# parallel_trans.net
KiCad netlist of a schematic drawn in EasyEDA Pro
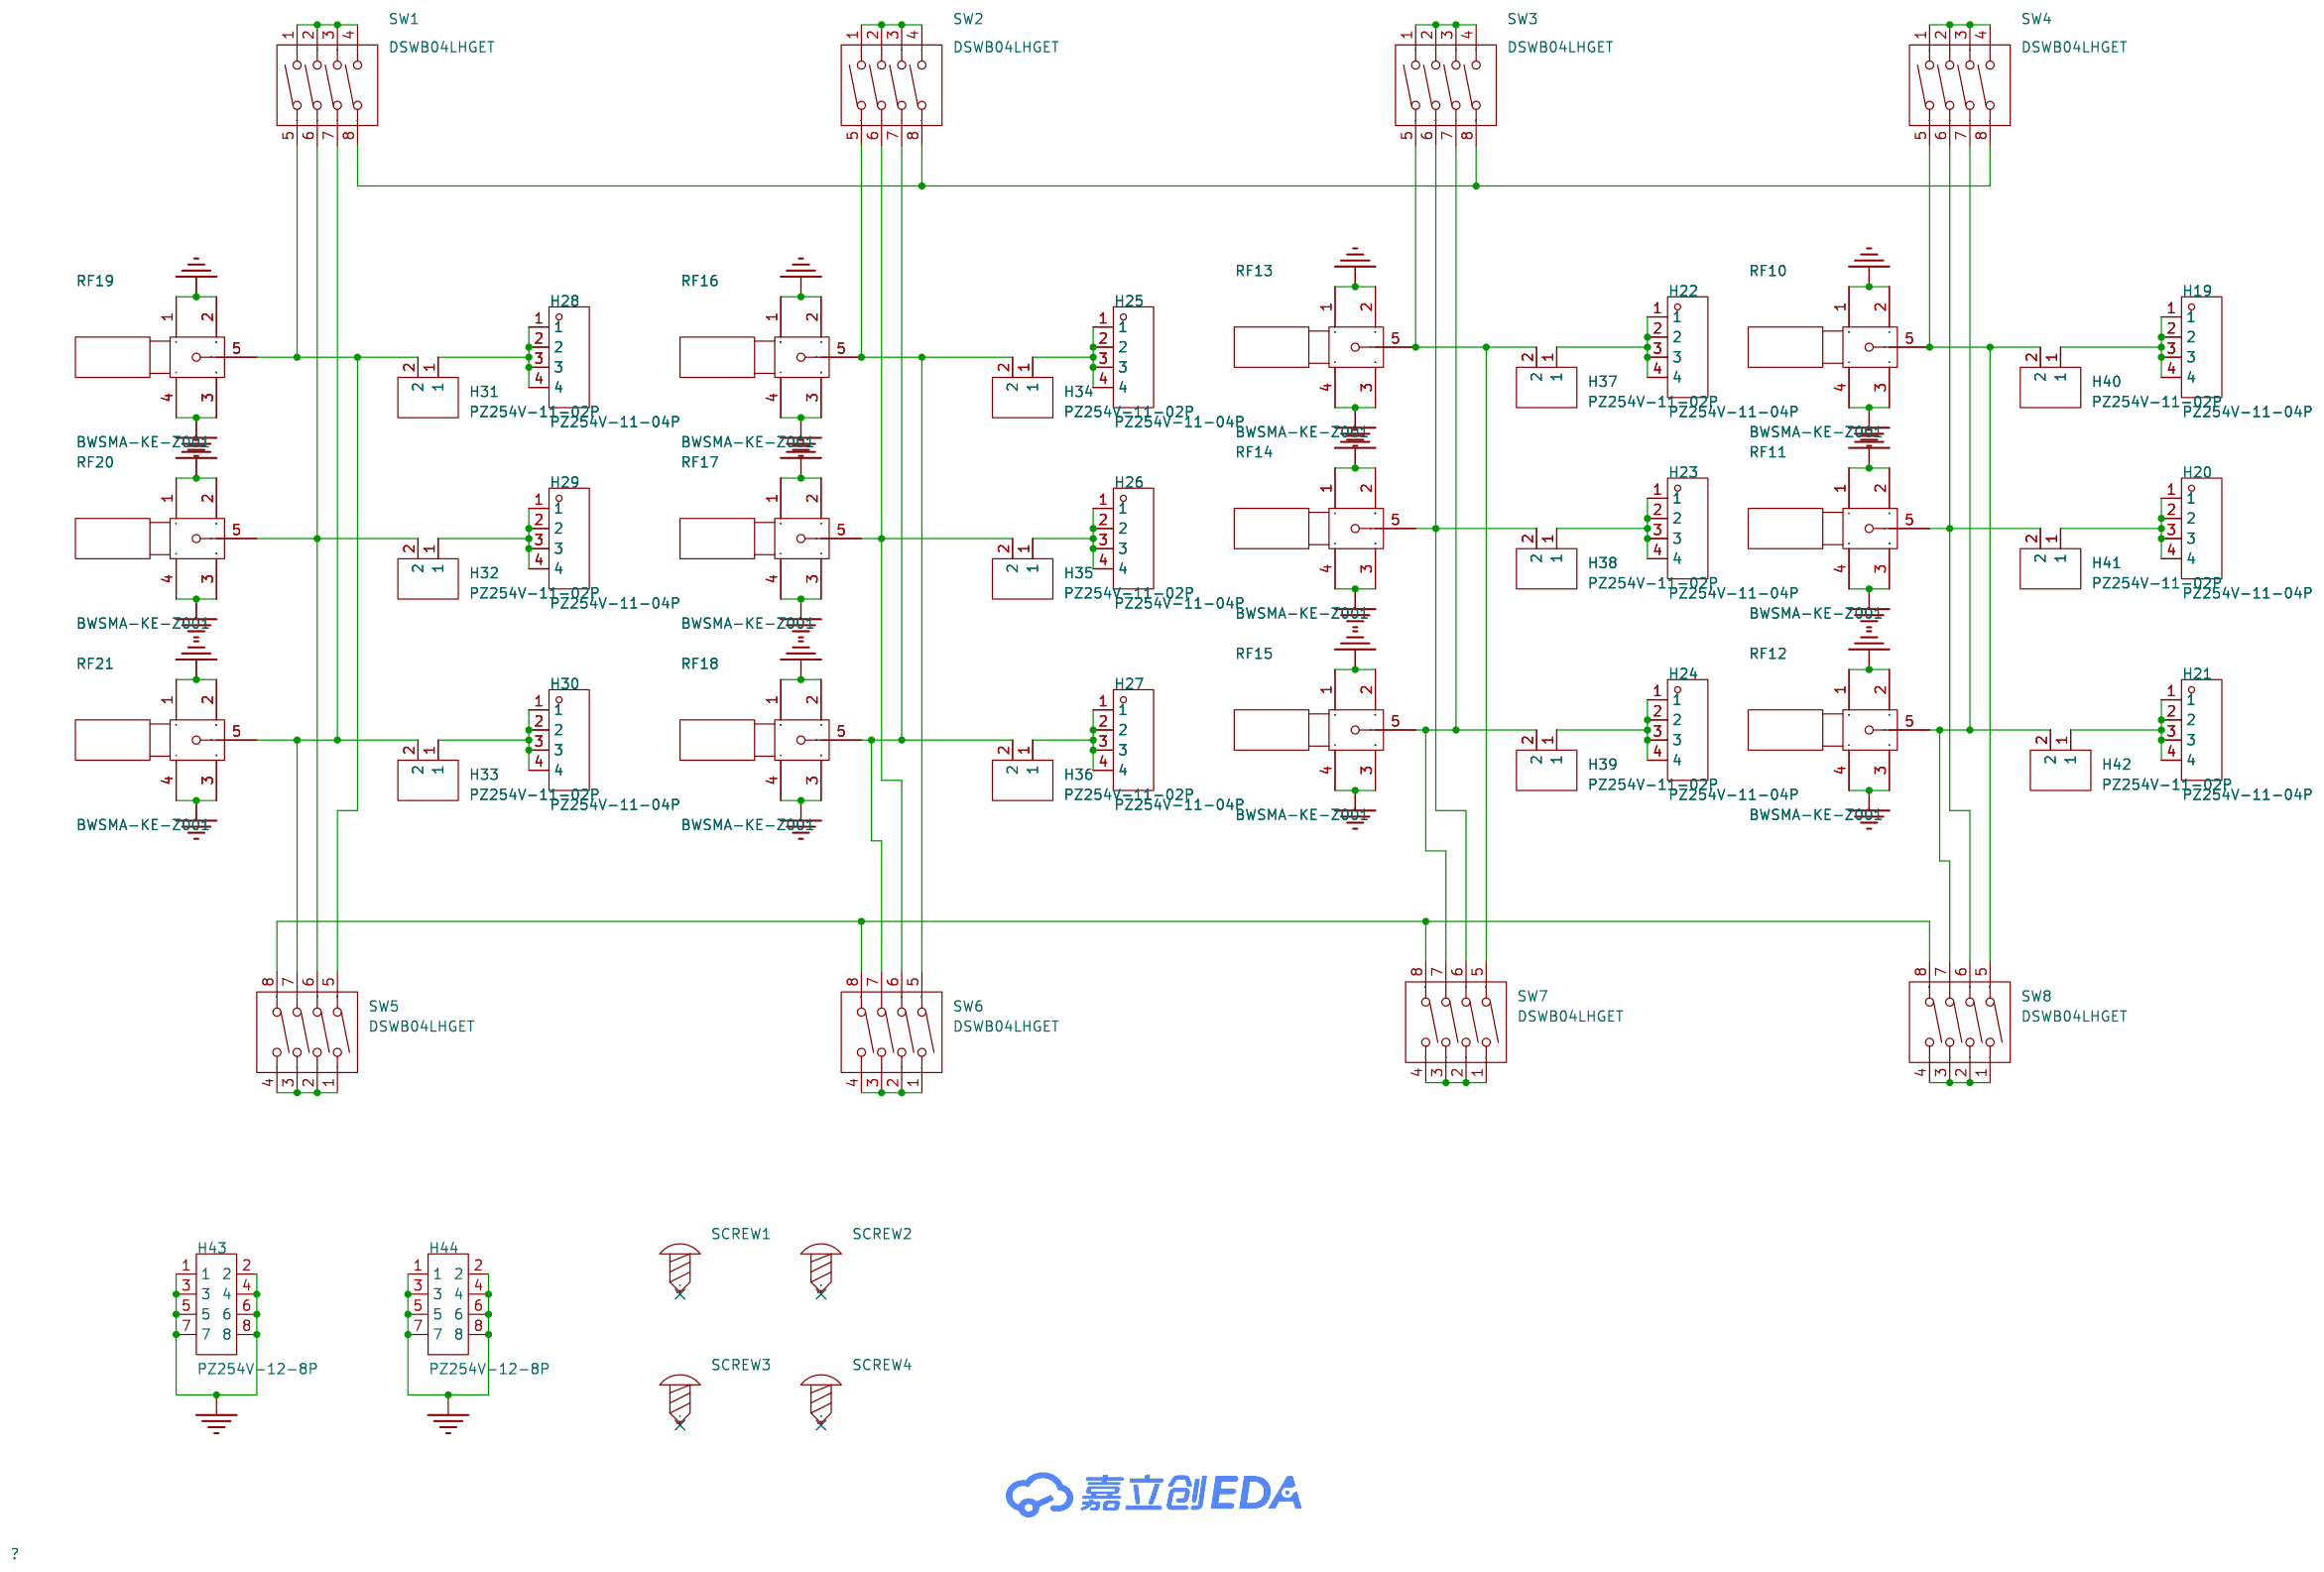
[diagram p0: schematic sheet]

(export (version "E")
  (design (tool "Eeschema 10.0.6"))
  (components
    (comp (ref "H19")
      (value "PZ254V-11-04P")
      (footprint "easyedapro:HDR-TH_4P-P2.54-V-M")
      (fields (field (name "Manufacturer") "XFCN(兴飞)"))
      (libsource (lib "easyedapro") (part "PZ254V-11-04P_C2691448"))
    )
    (comp (ref "H20")
      (value "PZ254V-11-04P")
      (footprint "easyedapro:HDR-TH_4P-P2.54-V-M")
      (fields (field (name "Manufacturer") "XFCN(兴飞)"))
      (libsource (lib "easyedapro") (part "PZ254V-11-04P_C2691448"))
    )
    (comp (ref "H21")
      (value "PZ254V-11-04P")
      (footprint "easyedapro:HDR-TH_4P-P2.54-V-M")
      (fields (field (name "Manufacturer") "XFCN(兴飞)"))
      (libsource (lib "easyedapro") (part "PZ254V-11-04P_C2691448"))
    )
    (comp (ref "H22")
      (value "PZ254V-11-04P")
      (footprint "easyedapro:HDR-TH_4P-P2.54-V-M")
      (fields (field (name "Manufacturer") "XFCN(兴飞)"))
      (libsource (lib "easyedapro") (part "PZ254V-11-04P_C2691448"))
    )
    (comp (ref "H23")
      (value "PZ254V-11-04P")
      (footprint "easyedapro:HDR-TH_4P-P2.54-V-M")
      (fields (field (name "Manufacturer") "XFCN(兴飞)"))
      (libsource (lib "easyedapro") (part "PZ254V-11-04P_C2691448"))
    )
    (comp (ref "H24")
      (value "PZ254V-11-04P")
      (footprint "easyedapro:HDR-TH_4P-P2.54-V-M")
      (fields (field (name "Manufacturer") "XFCN(兴飞)"))
      (libsource (lib "easyedapro") (part "PZ254V-11-04P_C2691448"))
    )
    (comp (ref "H25")
      (value "PZ254V-11-04P")
      (footprint "easyedapro:HDR-TH_4P-P2.54-V-M")
      (fields (field (name "Manufacturer") "XFCN(兴飞)"))
      (libsource (lib "easyedapro") (part "PZ254V-11-04P_C2691448"))
    )
    (comp (ref "H26")
      (value "PZ254V-11-04P")
      (footprint "easyedapro:HDR-TH_4P-P2.54-V-M")
      (fields (field (name "Manufacturer") "XFCN(兴飞)"))
      (libsource (lib "easyedapro") (part "PZ254V-11-04P_C2691448"))
    )
    (comp (ref "H27")
      (value "PZ254V-11-04P")
      (footprint "easyedapro:HDR-TH_4P-P2.54-V-M")
      (fields (field (name "Manufacturer") "XFCN(兴飞)"))
      (libsource (lib "easyedapro") (part "PZ254V-11-04P_C2691448"))
    )
    (comp (ref "H28")
      (value "PZ254V-11-04P")
      (footprint "easyedapro:HDR-TH_4P-P2.54-V-M")
      (fields (field (name "Manufacturer") "XFCN(兴飞)"))
      (libsource (lib "easyedapro") (part "PZ254V-11-04P_C2691448"))
    )
    (comp (ref "H29")
      (value "PZ254V-11-04P")
      (footprint "easyedapro:HDR-TH_4P-P2.54-V-M")
      (fields (field (name "Manufacturer") "XFCN(兴飞)"))
      (libsource (lib "easyedapro") (part "PZ254V-11-04P_C2691448"))
    )
    (comp (ref "H30")
      (value "PZ254V-11-04P")
      (footprint "easyedapro:HDR-TH_4P-P2.54-V-M")
      (fields (field (name "Manufacturer") "XFCN(兴飞)"))
      (libsource (lib "easyedapro") (part "PZ254V-11-04P_C2691448"))
    )
    (comp (ref "H31")
      (value "PZ254V-11-02P")
      (footprint "easyedapro:HDR-TH_2P-P2.54-V-M")
      (fields (field (name "Manufacturer") "XFCN(兴飞)"))
      (libsource (lib "easyedapro") (part "PZ254V-11-02P"))
    )
    (comp (ref "H32")
      (value "PZ254V-11-02P")
      (footprint "easyedapro:HDR-TH_2P-P2.54-V-M")
      (fields (field (name "Manufacturer") "XFCN(兴飞)"))
      (libsource (lib "easyedapro") (part "PZ254V-11-02P"))
    )
    (comp (ref "H33")
      (value "PZ254V-11-02P")
      (footprint "easyedapro:HDR-TH_2P-P2.54-V-M")
      (fields (field (name "Manufacturer") "XFCN(兴飞)"))
      (libsource (lib "easyedapro") (part "PZ254V-11-02P"))
    )
    (comp (ref "H34")
      (value "PZ254V-11-02P")
      (footprint "easyedapro:HDR-TH_2P-P2.54-V-M")
      (fields (field (name "Manufacturer") "XFCN(兴飞)"))
      (libsource (lib "easyedapro") (part "PZ254V-11-02P"))
    )
    (comp (ref "H35")
      (value "PZ254V-11-02P")
      (footprint "easyedapro:HDR-TH_2P-P2.54-V-M")
      (fields (field (name "Manufacturer") "XFCN(兴飞)"))
      (libsource (lib "easyedapro") (part "PZ254V-11-02P"))
    )
    (comp (ref "H36")
      (value "PZ254V-11-02P")
      (footprint "easyedapro:HDR-TH_2P-P2.54-V-M")
      (fields (field (name "Manufacturer") "XFCN(兴飞)"))
      (libsource (lib "easyedapro") (part "PZ254V-11-02P"))
    )
    (comp (ref "H37")
      (value "PZ254V-11-02P")
      (footprint "easyedapro:HDR-TH_2P-P2.54-V-M")
      (fields (field (name "Manufacturer") "XFCN(兴飞)"))
      (libsource (lib "easyedapro") (part "PZ254V-11-02P"))
    )
    (comp (ref "H38")
      (value "PZ254V-11-02P")
      (footprint "easyedapro:HDR-TH_2P-P2.54-V-M")
      (fields (field (name "Manufacturer") "XFCN(兴飞)"))
      (libsource (lib "easyedapro") (part "PZ254V-11-02P"))
    )
    (comp (ref "H39")
      (value "PZ254V-11-02P")
      (footprint "easyedapro:HDR-TH_2P-P2.54-V-M")
      (fields (field (name "Manufacturer") "XFCN(兴飞)"))
      (libsource (lib "easyedapro") (part "PZ254V-11-02P"))
    )
    (comp (ref "H40")
      (value "PZ254V-11-02P")
      (footprint "easyedapro:HDR-TH_2P-P2.54-V-M")
      (fields (field (name "Manufacturer") "XFCN(兴飞)"))
      (libsource (lib "easyedapro") (part "PZ254V-11-02P"))
    )
    (comp (ref "H41")
      (value "PZ254V-11-02P")
      (footprint "easyedapro:HDR-TH_2P-P2.54-V-M")
      (fields (field (name "Manufacturer") "XFCN(兴飞)"))
      (libsource (lib "easyedapro") (part "PZ254V-11-02P"))
    )
    (comp (ref "H42")
      (value "PZ254V-11-02P")
      (footprint "easyedapro:HDR-TH_2P-P2.54-V-M")
      (fields (field (name "Manufacturer") "XFCN(兴飞)"))
      (libsource (lib "easyedapro") (part "PZ254V-11-02P"))
    )
    (comp (ref "H43")
      (value "PZ254V-12-8P")
      (footprint "easyedapro:HDR-TH_8P-P2.54-V-M-R2-C4-S2.54")
      (fields (field (name "Manufacturer") "XFCN(兴飞)"))
      (libsource (lib "easyedapro") (part "PZ254V-12-8P"))
    )
    (comp (ref "H44")
      (value "PZ254V-12-8P")
      (footprint "easyedapro:HDR-TH_8P-P2.54-V-M-R2-C4-S2.54")
      (fields (field (name "Manufacturer") "XFCN(兴飞)"))
      (libsource (lib "easyedapro") (part "PZ254V-12-8P"))
    )
    (comp (ref "RF10")
      (value "BWSMA-KE-Z001")
      (footprint "easyedapro:SMA-TH_BWSMA-KE-Z001")
      (fields (field (name "Manufacturer") "BAT WIRELESS(蝙蝠无线)"))
      (libsource (lib "easyedapro") (part "BWSMA-KE-Z001"))
    )
    (comp (ref "RF11")
      (value "BWSMA-KE-Z001")
      (footprint "easyedapro:SMA-TH_BWSMA-KE-Z001")
      (fields (field (name "Manufacturer") "BAT WIRELESS(蝙蝠无线)"))
      (libsource (lib "easyedapro") (part "BWSMA-KE-Z001"))
    )
    (comp (ref "RF12")
      (value "BWSMA-KE-Z001")
      (footprint "easyedapro:SMA-TH_BWSMA-KE-Z001")
      (fields (field (name "Manufacturer") "BAT WIRELESS(蝙蝠无线)"))
      (libsource (lib "easyedapro") (part "BWSMA-KE-Z001"))
    )
    (comp (ref "RF13")
      (value "BWSMA-KE-Z001")
      (footprint "easyedapro:SMA-TH_BWSMA-KE-Z001")
      (fields (field (name "Manufacturer") "BAT WIRELESS(蝙蝠无线)"))
      (libsource (lib "easyedapro") (part "BWSMA-KE-Z001"))
    )
    (comp (ref "RF14")
      (value "BWSMA-KE-Z001")
      (footprint "easyedapro:SMA-TH_BWSMA-KE-Z001")
      (fields (field (name "Manufacturer") "BAT WIRELESS(蝙蝠无线)"))
      (libsource (lib "easyedapro") (part "BWSMA-KE-Z001"))
    )
    (comp (ref "RF15")
      (value "BWSMA-KE-Z001")
      (footprint "easyedapro:SMA-TH_BWSMA-KE-Z001")
      (fields (field (name "Manufacturer") "BAT WIRELESS(蝙蝠无线)"))
      (libsource (lib "easyedapro") (part "BWSMA-KE-Z001"))
    )
    (comp (ref "RF16")
      (value "BWSMA-KE-Z001")
      (footprint "easyedapro:SMA-TH_BWSMA-KE-Z001")
      (fields (field (name "Manufacturer") "BAT WIRELESS(蝙蝠无线)"))
      (libsource (lib "easyedapro") (part "BWSMA-KE-Z001"))
    )
    (comp (ref "RF17")
      (value "BWSMA-KE-Z001")
      (footprint "easyedapro:SMA-TH_BWSMA-KE-Z001")
      (fields (field (name "Manufacturer") "BAT WIRELESS(蝙蝠无线)"))
      (libsource (lib "easyedapro") (part "BWSMA-KE-Z001"))
    )
    (comp (ref "RF18")
      (value "BWSMA-KE-Z001")
      (footprint "easyedapro:SMA-TH_BWSMA-KE-Z001")
      (fields (field (name "Manufacturer") "BAT WIRELESS(蝙蝠无线)"))
      (libsource (lib "easyedapro") (part "BWSMA-KE-Z001"))
    )
    (comp (ref "RF19")
      (value "BWSMA-KE-Z001")
      (footprint "easyedapro:SMA-TH_BWSMA-KE-Z001")
      (fields (field (name "Manufacturer") "BAT WIRELESS(蝙蝠无线)"))
      (libsource (lib "easyedapro") (part "BWSMA-KE-Z001"))
    )
    (comp (ref "RF20")
      (value "BWSMA-KE-Z001")
      (footprint "easyedapro:SMA-TH_BWSMA-KE-Z001")
      (fields (field (name "Manufacturer") "BAT WIRELESS(蝙蝠无线)"))
      (libsource (lib "easyedapro") (part "BWSMA-KE-Z001"))
    )
    (comp (ref "RF21")
      (value "BWSMA-KE-Z001")
      (footprint "easyedapro:SMA-TH_BWSMA-KE-Z001")
      (fields (field (name "Manufacturer") "BAT WIRELESS(蝙蝠无线)"))
      (libsource (lib "easyedapro") (part "BWSMA-KE-Z001"))
    )
    (comp (ref "SCREW1")
      (value "~")
      (footprint "easyedapro:M3螺丝")
      (libsource (lib "easyedapro") (part "螺丝孔"))
    )
    (comp (ref "SCREW2")
      (value "~")
      (footprint "easyedapro:M3螺丝")
      (libsource (lib "easyedapro") (part "螺丝孔"))
    )
    (comp (ref "SCREW3")
      (value "~")
      (footprint "easyedapro:M3螺丝")
      (libsource (lib "easyedapro") (part "螺丝孔"))
    )
    (comp (ref "SCREW4")
      (value "~")
      (footprint "easyedapro:M3螺丝")
      (libsource (lib "easyedapro") (part "螺丝孔"))
    )
    (comp (ref "SW1")
      (value "DSWB04LHGET")
      (footprint "easyedapro:SW-TH_DSWB04LHGET")
      (description "类型:平拨,凸起式;电路结构:单刀单掷;开关位数:4位;使用寿命:-;颜色:红色;")
      (fields (field (name "Manufacturer") "YE"))
      (libsource (lib "easyedapro") (part "DSWB04LHGET"))
    )
    (comp (ref "SW2")
      (value "DSWB04LHGET")
      (footprint "easyedapro:SW-TH_DSWB04LHGET")
      (description "类型:平拨,凸起式;电路结构:单刀单掷;开关位数:4位;使用寿命:-;颜色:红色;")
      (fields (field (name "Manufacturer") "YE"))
      (libsource (lib "easyedapro") (part "DSWB04LHGET"))
    )
    (comp (ref "SW3")
      (value "DSWB04LHGET")
      (footprint "easyedapro:SW-TH_DSWB04LHGET")
      (description "类型:平拨,凸起式;电路结构:单刀单掷;开关位数:4位;使用寿命:-;颜色:红色;")
      (fields (field (name "Manufacturer") "YE"))
      (libsource (lib "easyedapro") (part "DSWB04LHGET"))
    )
    (comp (ref "SW4")
      (value "DSWB04LHGET")
      (footprint "easyedapro:SW-TH_DSWB04LHGET")
      (description "类型:平拨,凸起式;电路结构:单刀单掷;开关位数:4位;使用寿命:-;颜色:红色;")
      (fields (field (name "Manufacturer") "YE"))
      (libsource (lib "easyedapro") (part "DSWB04LHGET"))
    )
    (comp (ref "SW5")
      (value "DSWB04LHGET")
      (footprint "easyedapro:SW-TH_DSWB04LHGET")
      (description "类型:平拨,凸起式;电路结构:单刀单掷;开关位数:4位;使用寿命:-;颜色:红色;")
      (fields (field (name "Manufacturer") "YE"))
      (libsource (lib "easyedapro") (part "DSWB04LHGET"))
    )
    (comp (ref "SW6")
      (value "DSWB04LHGET")
      (footprint "easyedapro:SW-TH_DSWB04LHGET")
      (description "类型:平拨,凸起式;电路结构:单刀单掷;开关位数:4位;使用寿命:-;颜色:红色;")
      (fields (field (name "Manufacturer") "YE"))
      (libsource (lib "easyedapro") (part "DSWB04LHGET"))
    )
    (comp (ref "SW7")
      (value "DSWB04LHGET")
      (footprint "easyedapro:SW-TH_DSWB04LHGET")
      (description "类型:平拨,凸起式;电路结构:单刀单掷;开关位数:4位;使用寿命:-;颜色:红色;")
      (fields (field (name "Manufacturer") "YE"))
      (libsource (lib "easyedapro") (part "DSWB04LHGET"))
    )
    (comp (ref "SW8")
      (value "DSWB04LHGET")
      (footprint "easyedapro:SW-TH_DSWB04LHGET")
      (description "类型:平拨,凸起式;电路结构:单刀单掷;开关位数:4位;使用寿命:-;颜色:红色;")
      (fields (field (name "Manufacturer") "YE"))
      (libsource (lib "easyedapro") (part "DSWB04LHGET"))
    )
  )
  (nets
    (net (code "1") (name "GND") (class "Default")
      (node (ref "H43") (pin "1") (pinfunction "1_1") (pintype "unspecified"))
      (node (ref "H43") (pin "2") (pinfunction "2_2") (pintype "unspecified"))
      (node (ref "H43") (pin "3") (pinfunction "3_3") (pintype "unspecified"))
      (node (ref "H43") (pin "4") (pinfunction "4_4") (pintype "unspecified"))
      (node (ref "H43") (pin "5") (pinfunction "5_5") (pintype "unspecified"))
      (node (ref "H43") (pin "6") (pinfunction "6_6") (pintype "unspecified"))
      (node (ref "H43") (pin "7") (pinfunction "7_7") (pintype "unspecified"))
      (node (ref "H43") (pin "8") (pinfunction "8_8") (pintype "unspecified"))
      (node (ref "H44") (pin "1") (pinfunction "1_1") (pintype "unspecified"))
      (node (ref "H44") (pin "2") (pinfunction "2_2") (pintype "unspecified"))
      (node (ref "H44") (pin "3") (pinfunction "3_3") (pintype "unspecified"))
      (node (ref "H44") (pin "4") (pinfunction "4_4") (pintype "unspecified"))
      (node (ref "H44") (pin "5") (pinfunction "5_5") (pintype "unspecified"))
      (node (ref "H44") (pin "6") (pinfunction "6_6") (pintype "unspecified"))
      (node (ref "H44") (pin "7") (pinfunction "7_7") (pintype "unspecified"))
      (node (ref "H44") (pin "8") (pinfunction "8_8") (pintype "unspecified"))
      (node (ref "RF10") (pin "1") (pinfunction "1_1") (pintype "unspecified"))
      (node (ref "RF10") (pin "2") (pinfunction "2_2") (pintype "unspecified"))
      (node (ref "RF10") (pin "3") (pinfunction "3_3") (pintype "unspecified"))
      (node (ref "RF10") (pin "4") (pinfunction "4_4") (pintype "unspecified"))
      (node (ref "RF11") (pin "1") (pinfunction "1_1") (pintype "unspecified"))
      (node (ref "RF11") (pin "2") (pinfunction "2_2") (pintype "unspecified"))
      (node (ref "RF11") (pin "3") (pinfunction "3_3") (pintype "unspecified"))
      (node (ref "RF11") (pin "4") (pinfunction "4_4") (pintype "unspecified"))
      (node (ref "RF12") (pin "1") (pinfunction "1_1") (pintype "unspecified"))
      (node (ref "RF12") (pin "2") (pinfunction "2_2") (pintype "unspecified"))
      (node (ref "RF12") (pin "3") (pinfunction "3_3") (pintype "unspecified"))
      (node (ref "RF12") (pin "4") (pinfunction "4_4") (pintype "unspecified"))
      (node (ref "RF13") (pin "1") (pinfunction "1_1") (pintype "unspecified"))
      (node (ref "RF13") (pin "2") (pinfunction "2_2") (pintype "unspecified"))
      (node (ref "RF13") (pin "3") (pinfunction "3_3") (pintype "unspecified"))
      (node (ref "RF13") (pin "4") (pinfunction "4_4") (pintype "unspecified"))
      (node (ref "RF14") (pin "1") (pinfunction "1_1") (pintype "unspecified"))
      (node (ref "RF14") (pin "2") (pinfunction "2_2") (pintype "unspecified"))
      (node (ref "RF14") (pin "3") (pinfunction "3_3") (pintype "unspecified"))
      (node (ref "RF14") (pin "4") (pinfunction "4_4") (pintype "unspecified"))
      (node (ref "RF15") (pin "1") (pinfunction "1_1") (pintype "unspecified"))
      (node (ref "RF15") (pin "2") (pinfunction "2_2") (pintype "unspecified"))
      (node (ref "RF15") (pin "3") (pinfunction "3_3") (pintype "unspecified"))
      (node (ref "RF15") (pin "4") (pinfunction "4_4") (pintype "unspecified"))
      (node (ref "RF16") (pin "1") (pinfunction "1_1") (pintype "unspecified"))
      (node (ref "RF16") (pin "2") (pinfunction "2_2") (pintype "unspecified"))
      (node (ref "RF16") (pin "3") (pinfunction "3_3") (pintype "unspecified"))
      (node (ref "RF16") (pin "4") (pinfunction "4_4") (pintype "unspecified"))
      (node (ref "RF17") (pin "1") (pinfunction "1_1") (pintype "unspecified"))
      (node (ref "RF17") (pin "2") (pinfunction "2_2") (pintype "unspecified"))
      (node (ref "RF17") (pin "3") (pinfunction "3_3") (pintype "unspecified"))
      (node (ref "RF17") (pin "4") (pinfunction "4_4") (pintype "unspecified"))
      (node (ref "RF18") (pin "1") (pinfunction "1_1") (pintype "unspecified"))
      (node (ref "RF18") (pin "2") (pinfunction "2_2") (pintype "unspecified"))
      (node (ref "RF18") (pin "3") (pinfunction "3_3") (pintype "unspecified"))
      (node (ref "RF18") (pin "4") (pinfunction "4_4") (pintype "unspecified"))
      (node (ref "RF19") (pin "1") (pinfunction "1_1") (pintype "unspecified"))
      (node (ref "RF19") (pin "2") (pinfunction "2_2") (pintype "unspecified"))
      (node (ref "RF19") (pin "3") (pinfunction "3_3") (pintype "unspecified"))
      (node (ref "RF19") (pin "4") (pinfunction "4_4") (pintype "unspecified"))
      (node (ref "RF20") (pin "1") (pinfunction "1_1") (pintype "unspecified"))
      (node (ref "RF20") (pin "2") (pinfunction "2_2") (pintype "unspecified"))
      (node (ref "RF20") (pin "3") (pinfunction "3_3") (pintype "unspecified"))
      (node (ref "RF20") (pin "4") (pinfunction "4_4") (pintype "unspecified"))
      (node (ref "RF21") (pin "1") (pinfunction "1_1") (pintype "unspecified"))
      (node (ref "RF21") (pin "2") (pinfunction "2_2") (pintype "unspecified"))
      (node (ref "RF21") (pin "3") (pinfunction "3_3") (pintype "unspecified"))
      (node (ref "RF21") (pin "4") (pinfunction "4_4") (pintype "unspecified"))
    )
    (net (code "2") (name "Net-(H19-Pad1)") (class "Default")
      (node (ref "H19") (pin "1") (pinfunction "1_1") (pintype "unspecified"))
      (node (ref "H19") (pin "2") (pinfunction "2_2") (pintype "unspecified"))
      (node (ref "H19") (pin "3") (pinfunction "3_3") (pintype "unspecified"))
      (node (ref "H19") (pin "4") (pinfunction "4_4") (pintype "unspecified"))
      (node (ref "H40") (pin "1") (pinfunction "1_1") (pintype "unspecified"))
    )
    (net (code "3") (name "Net-(H20-Pad1)") (class "Default")
      (node (ref "H20") (pin "1") (pinfunction "1_1") (pintype "unspecified"))
      (node (ref "H20") (pin "2") (pinfunction "2_2") (pintype "unspecified"))
      (node (ref "H20") (pin "3") (pinfunction "3_3") (pintype "unspecified"))
      (node (ref "H20") (pin "4") (pinfunction "4_4") (pintype "unspecified"))
      (node (ref "H41") (pin "1") (pinfunction "1_1") (pintype "unspecified"))
    )
    (net (code "4") (name "Net-(H21-Pad1)") (class "Default")
      (node (ref "H21") (pin "1") (pinfunction "1_1") (pintype "unspecified"))
      (node (ref "H21") (pin "2") (pinfunction "2_2") (pintype "unspecified"))
      (node (ref "H21") (pin "3") (pinfunction "3_3") (pintype "unspecified"))
      (node (ref "H21") (pin "4") (pinfunction "4_4") (pintype "unspecified"))
      (node (ref "H42") (pin "1") (pinfunction "1_1") (pintype "unspecified"))
    )
    (net (code "5") (name "Net-(H22-Pad1)") (class "Default")
      (node (ref "H22") (pin "1") (pinfunction "1_1") (pintype "unspecified"))
      (node (ref "H22") (pin "2") (pinfunction "2_2") (pintype "unspecified"))
      (node (ref "H22") (pin "3") (pinfunction "3_3") (pintype "unspecified"))
      (node (ref "H22") (pin "4") (pinfunction "4_4") (pintype "unspecified"))
      (node (ref "H37") (pin "1") (pinfunction "1_1") (pintype "unspecified"))
    )
    (net (code "6") (name "Net-(H23-Pad1)") (class "Default")
      (node (ref "H23") (pin "1") (pinfunction "1_1") (pintype "unspecified"))
      (node (ref "H23") (pin "2") (pinfunction "2_2") (pintype "unspecified"))
      (node (ref "H23") (pin "3") (pinfunction "3_3") (pintype "unspecified"))
      (node (ref "H23") (pin "4") (pinfunction "4_4") (pintype "unspecified"))
      (node (ref "H38") (pin "1") (pinfunction "1_1") (pintype "unspecified"))
    )
    (net (code "7") (name "Net-(H24-Pad1)") (class "Default")
      (node (ref "H24") (pin "1") (pinfunction "1_1") (pintype "unspecified"))
      (node (ref "H24") (pin "2") (pinfunction "2_2") (pintype "unspecified"))
      (node (ref "H24") (pin "3") (pinfunction "3_3") (pintype "unspecified"))
      (node (ref "H24") (pin "4") (pinfunction "4_4") (pintype "unspecified"))
      (node (ref "H39") (pin "1") (pinfunction "1_1") (pintype "unspecified"))
    )
    (net (code "8") (name "Net-(H25-Pad1)") (class "Default")
      (node (ref "H25") (pin "1") (pinfunction "1_1") (pintype "unspecified"))
      (node (ref "H25") (pin "2") (pinfunction "2_2") (pintype "unspecified"))
      (node (ref "H25") (pin "3") (pinfunction "3_3") (pintype "unspecified"))
      (node (ref "H25") (pin "4") (pinfunction "4_4") (pintype "unspecified"))
      (node (ref "H34") (pin "1") (pinfunction "1_1") (pintype "unspecified"))
    )
    (net (code "9") (name "Net-(H26-Pad1)") (class "Default")
      (node (ref "H26") (pin "1") (pinfunction "1_1") (pintype "unspecified"))
      (node (ref "H26") (pin "2") (pinfunction "2_2") (pintype "unspecified"))
      (node (ref "H26") (pin "3") (pinfunction "3_3") (pintype "unspecified"))
      (node (ref "H26") (pin "4") (pinfunction "4_4") (pintype "unspecified"))
      (node (ref "H35") (pin "1") (pinfunction "1_1") (pintype "unspecified"))
    )
    (net (code "10") (name "Net-(H27-Pad1)") (class "Default")
      (node (ref "H27") (pin "1") (pinfunction "1_1") (pintype "unspecified"))
      (node (ref "H27") (pin "2") (pinfunction "2_2") (pintype "unspecified"))
      (node (ref "H27") (pin "3") (pinfunction "3_3") (pintype "unspecified"))
      (node (ref "H27") (pin "4") (pinfunction "4_4") (pintype "unspecified"))
      (node (ref "H36") (pin "1") (pinfunction "1_1") (pintype "unspecified"))
    )
    (net (code "11") (name "Net-(H28-Pad1)") (class "Default")
      (node (ref "H28") (pin "1") (pinfunction "1_1") (pintype "unspecified"))
      (node (ref "H28") (pin "2") (pinfunction "2_2") (pintype "unspecified"))
      (node (ref "H28") (pin "3") (pinfunction "3_3") (pintype "unspecified"))
      (node (ref "H28") (pin "4") (pinfunction "4_4") (pintype "unspecified"))
      (node (ref "H31") (pin "1") (pinfunction "1_1") (pintype "unspecified"))
    )
    (net (code "12") (name "Net-(H29-Pad1)") (class "Default")
      (node (ref "H29") (pin "1") (pinfunction "1_1") (pintype "unspecified"))
      (node (ref "H29") (pin "2") (pinfunction "2_2") (pintype "unspecified"))
      (node (ref "H29") (pin "3") (pinfunction "3_3") (pintype "unspecified"))
      (node (ref "H29") (pin "4") (pinfunction "4_4") (pintype "unspecified"))
      (node (ref "H32") (pin "1") (pinfunction "1_1") (pintype "unspecified"))
    )
    (net (code "13") (name "Net-(H30-Pad1)") (class "Default")
      (node (ref "H30") (pin "1") (pinfunction "1_1") (pintype "unspecified"))
      (node (ref "H30") (pin "2") (pinfunction "2_2") (pintype "unspecified"))
      (node (ref "H30") (pin "3") (pinfunction "3_3") (pintype "unspecified"))
      (node (ref "H30") (pin "4") (pinfunction "4_4") (pintype "unspecified"))
      (node (ref "H33") (pin "1") (pinfunction "1_1") (pintype "unspecified"))
    )
    (net (code "14") (name "Net-(H31-Pad2)") (class "Default")
      (node (ref "H31") (pin "2") (pinfunction "2_2") (pintype "unspecified"))
      (node (ref "RF19") (pin "5") (pinfunction "5_5") (pintype "unspecified"))
      (node (ref "SW1") (pin "5") (pinfunction "5_5") (pintype "unspecified"))
      (node (ref "SW5") (pin "5") (pinfunction "5_5") (pintype "unspecified"))
    )
    (net (code "15") (name "Net-(H32-Pad2)") (class "Default")
      (node (ref "H32") (pin "2") (pinfunction "2_2") (pintype "unspecified"))
      (node (ref "RF20") (pin "5") (pinfunction "5_5") (pintype "unspecified"))
      (node (ref "SW1") (pin "6") (pinfunction "6_6") (pintype "unspecified"))
      (node (ref "SW5") (pin "6") (pinfunction "6_6") (pintype "unspecified"))
    )
    (net (code "16") (name "Net-(H33-Pad2)") (class "Default")
      (node (ref "H33") (pin "2") (pinfunction "2_2") (pintype "unspecified"))
      (node (ref "RF21") (pin "5") (pinfunction "5_5") (pintype "unspecified"))
      (node (ref "SW1") (pin "7") (pinfunction "7_7") (pintype "unspecified"))
      (node (ref "SW5") (pin "7") (pinfunction "7_7") (pintype "unspecified"))
    )
    (net (code "17") (name "Net-(H34-Pad2)") (class "Default")
      (node (ref "H34") (pin "2") (pinfunction "2_2") (pintype "unspecified"))
      (node (ref "RF16") (pin "5") (pinfunction "5_5") (pintype "unspecified"))
      (node (ref "SW2") (pin "5") (pinfunction "5_5") (pintype "unspecified"))
      (node (ref "SW6") (pin "5") (pinfunction "5_5") (pintype "unspecified"))
    )
    (net (code "18") (name "Net-(H35-Pad2)") (class "Default")
      (node (ref "H35") (pin "2") (pinfunction "2_2") (pintype "unspecified"))
      (node (ref "RF17") (pin "5") (pinfunction "5_5") (pintype "unspecified"))
      (node (ref "SW2") (pin "6") (pinfunction "6_6") (pintype "unspecified"))
      (node (ref "SW6") (pin "6") (pinfunction "6_6") (pintype "unspecified"))
    )
    (net (code "19") (name "Net-(H36-Pad2)") (class "Default")
      (node (ref "H36") (pin "2") (pinfunction "2_2") (pintype "unspecified"))
      (node (ref "RF18") (pin "5") (pinfunction "5_5") (pintype "unspecified"))
      (node (ref "SW2") (pin "7") (pinfunction "7_7") (pintype "unspecified"))
      (node (ref "SW6") (pin "7") (pinfunction "7_7") (pintype "unspecified"))
    )
    (net (code "20") (name "Net-(H37-Pad2)") (class "Default")
      (node (ref "H37") (pin "2") (pinfunction "2_2") (pintype "unspecified"))
      (node (ref "RF13") (pin "5") (pinfunction "5_5") (pintype "unspecified"))
      (node (ref "SW3") (pin "5") (pinfunction "5_5") (pintype "unspecified"))
      (node (ref "SW7") (pin "5") (pinfunction "5_5") (pintype "unspecified"))
    )
    (net (code "21") (name "Net-(H38-Pad2)") (class "Default")
      (node (ref "H38") (pin "2") (pinfunction "2_2") (pintype "unspecified"))
      (node (ref "RF14") (pin "5") (pinfunction "5_5") (pintype "unspecified"))
      (node (ref "SW3") (pin "6") (pinfunction "6_6") (pintype "unspecified"))
      (node (ref "SW7") (pin "6") (pinfunction "6_6") (pintype "unspecified"))
    )
    (net (code "22") (name "Net-(H39-Pad2)") (class "Default")
      (node (ref "H39") (pin "2") (pinfunction "2_2") (pintype "unspecified"))
      (node (ref "RF15") (pin "5") (pinfunction "5_5") (pintype "unspecified"))
      (node (ref "SW3") (pin "7") (pinfunction "7_7") (pintype "unspecified"))
      (node (ref "SW7") (pin "7") (pinfunction "7_7") (pintype "unspecified"))
    )
    (net (code "23") (name "Net-(H40-Pad2)") (class "Default")
      (node (ref "H40") (pin "2") (pinfunction "2_2") (pintype "unspecified"))
      (node (ref "RF10") (pin "5") (pinfunction "5_5") (pintype "unspecified"))
      (node (ref "SW4") (pin "5") (pinfunction "5_5") (pintype "unspecified"))
      (node (ref "SW8") (pin "5") (pinfunction "5_5") (pintype "unspecified"))
    )
    (net (code "24") (name "Net-(H41-Pad2)") (class "Default")
      (node (ref "H41") (pin "2") (pinfunction "2_2") (pintype "unspecified"))
      (node (ref "RF11") (pin "5") (pinfunction "5_5") (pintype "unspecified"))
      (node (ref "SW4") (pin "6") (pinfunction "6_6") (pintype "unspecified"))
      (node (ref "SW8") (pin "6") (pinfunction "6_6") (pintype "unspecified"))
    )
    (net (code "25") (name "Net-(H42-Pad2)") (class "Default")
      (node (ref "H42") (pin "2") (pinfunction "2_2") (pintype "unspecified"))
      (node (ref "RF12") (pin "5") (pinfunction "5_5") (pintype "unspecified"))
      (node (ref "SW4") (pin "7") (pinfunction "7_7") (pintype "unspecified"))
      (node (ref "SW8") (pin "7") (pinfunction "7_7") (pintype "unspecified"))
    )
    (net (code "26") (name "Net-(SW1-Pad1)") (class "Default")
      (node (ref "SW1") (pin "1") (pinfunction "1_1") (pintype "unspecified"))
      (node (ref "SW1") (pin "2") (pinfunction "2_2") (pintype "unspecified"))
      (node (ref "SW1") (pin "3") (pinfunction "3_3") (pintype "unspecified"))
      (node (ref "SW1") (pin "4") (pinfunction "4_4") (pintype "unspecified"))
    )
    (net (code "27") (name "Net-(SW1-Pad8)") (class "Default")
      (node (ref "SW1") (pin "8") (pinfunction "8_8") (pintype "unspecified"))
      (node (ref "SW2") (pin "8") (pinfunction "8_8") (pintype "unspecified"))
      (node (ref "SW3") (pin "8") (pinfunction "8_8") (pintype "unspecified"))
      (node (ref "SW4") (pin "8") (pinfunction "8_8") (pintype "unspecified"))
    )
    (net (code "28") (name "Net-(SW2-Pad1)") (class "Default")
      (node (ref "SW2") (pin "1") (pinfunction "1_1") (pintype "unspecified"))
      (node (ref "SW2") (pin "2") (pinfunction "2_2") (pintype "unspecified"))
      (node (ref "SW2") (pin "3") (pinfunction "3_3") (pintype "unspecified"))
      (node (ref "SW2") (pin "4") (pinfunction "4_4") (pintype "unspecified"))
    )
    (net (code "29") (name "Net-(SW3-Pad1)") (class "Default")
      (node (ref "SW3") (pin "1") (pinfunction "1_1") (pintype "unspecified"))
      (node (ref "SW3") (pin "2") (pinfunction "2_2") (pintype "unspecified"))
      (node (ref "SW3") (pin "3") (pinfunction "3_3") (pintype "unspecified"))
      (node (ref "SW3") (pin "4") (pinfunction "4_4") (pintype "unspecified"))
    )
    (net (code "30") (name "Net-(SW4-Pad1)") (class "Default")
      (node (ref "SW4") (pin "1") (pinfunction "1_1") (pintype "unspecified"))
      (node (ref "SW4") (pin "2") (pinfunction "2_2") (pintype "unspecified"))
      (node (ref "SW4") (pin "3") (pinfunction "3_3") (pintype "unspecified"))
      (node (ref "SW4") (pin "4") (pinfunction "4_4") (pintype "unspecified"))
    )
    (net (code "31") (name "Net-(SW5-Pad1)") (class "Default")
      (node (ref "SW5") (pin "1") (pinfunction "1_1") (pintype "unspecified"))
      (node (ref "SW5") (pin "2") (pinfunction "2_2") (pintype "unspecified"))
      (node (ref "SW5") (pin "3") (pinfunction "3_3") (pintype "unspecified"))
      (node (ref "SW5") (pin "4") (pinfunction "4_4") (pintype "unspecified"))
    )
    (net (code "32") (name "Net-(SW5-Pad8)") (class "Default")
      (node (ref "SW5") (pin "8") (pinfunction "8_8") (pintype "unspecified"))
      (node (ref "SW6") (pin "8") (pinfunction "8_8") (pintype "unspecified"))
      (node (ref "SW7") (pin "8") (pinfunction "8_8") (pintype "unspecified"))
      (node (ref "SW8") (pin "8") (pinfunction "8_8") (pintype "unspecified"))
    )
    (net (code "33") (name "Net-(SW6-Pad1)") (class "Default")
      (node (ref "SW6") (pin "1") (pinfunction "1_1") (pintype "unspecified"))
      (node (ref "SW6") (pin "2") (pinfunction "2_2") (pintype "unspecified"))
      (node (ref "SW6") (pin "3") (pinfunction "3_3") (pintype "unspecified"))
      (node (ref "SW6") (pin "4") (pinfunction "4_4") (pintype "unspecified"))
    )
    (net (code "34") (name "Net-(SW7-Pad1)") (class "Default")
      (node (ref "SW7") (pin "1") (pinfunction "1_1") (pintype "unspecified"))
      (node (ref "SW7") (pin "2") (pinfunction "2_2") (pintype "unspecified"))
      (node (ref "SW7") (pin "3") (pinfunction "3_3") (pintype "unspecified"))
      (node (ref "SW7") (pin "4") (pinfunction "4_4") (pintype "unspecified"))
    )
    (net (code "35") (name "Net-(SW8-Pad1)") (class "Default")
      (node (ref "SW8") (pin "1") (pinfunction "1_1") (pintype "unspecified"))
      (node (ref "SW8") (pin "2") (pinfunction "2_2") (pintype "unspecified"))
      (node (ref "SW8") (pin "3") (pinfunction "3_3") (pintype "unspecified"))
      (node (ref "SW8") (pin "4") (pinfunction "4_4") (pintype "unspecified"))
    )
    (net (code "36") (name "unconnected-(SCREW1-Pad1)") (class "Default")
      (node (ref "SCREW1") (pin "1") (pinfunction "1_1") (pintype "input+no_connect"))
    )
    (net (code "37") (name "unconnected-(SCREW2-Pad1)") (class "Default")
      (node (ref "SCREW2") (pin "1") (pinfunction "1_1") (pintype "input+no_connect"))
    )
    (net (code "38") (name "unconnected-(SCREW3-Pad1)") (class "Default")
      (node (ref "SCREW3") (pin "1") (pinfunction "1_1") (pintype "input+no_connect"))
    )
    (net (code "39") (name "unconnected-(SCREW4-Pad1)") (class "Default")
      (node (ref "SCREW4") (pin "1") (pinfunction "1_1") (pintype "input+no_connect"))
    )
  )
)
